# ExtensionConnector.net
KiCad netlist of a schematic drawn in Altium Designer
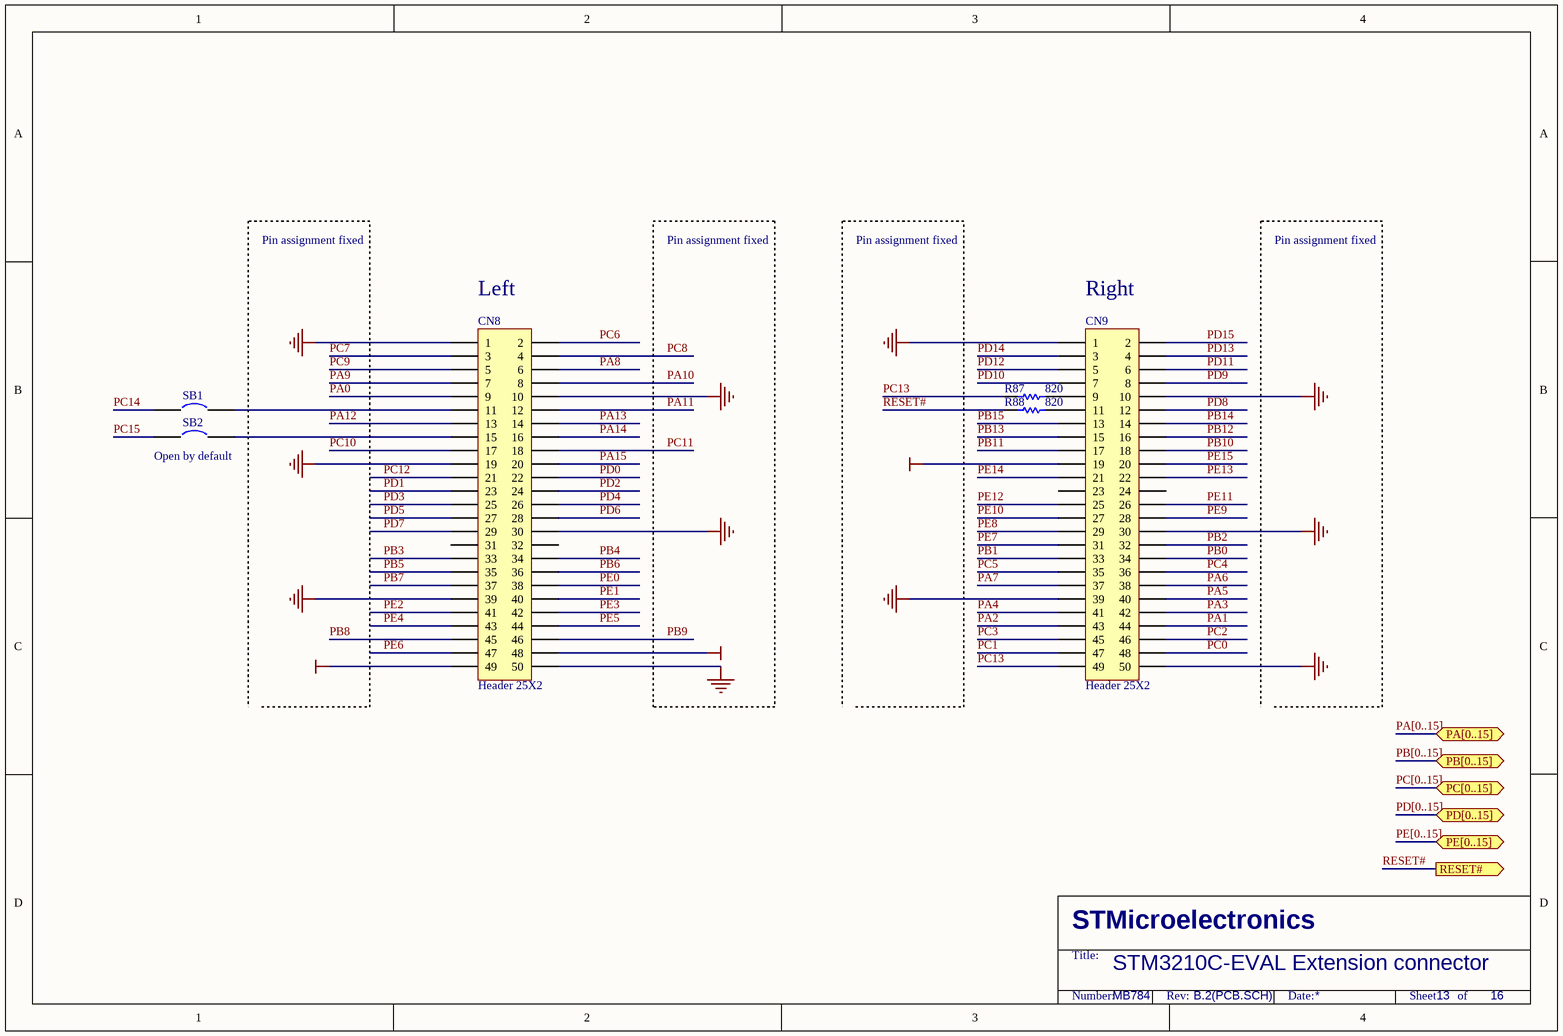
[diagram p0: ExtensionConnector.SchDoc]

(export (version "E")
  (design (tool "Eeschema 10.0.6"))
  (components
    (comp (ref "CN8")
      (value "Header 25X2")
      (footprint "2*25P")
      (description "Header, 25-Pin, Dual row")
      (fields (field (name "PUBLISHER") "Altium Limited"))
      (libsource (lib "Miscellaneous Connectors") (part "Header 25X2"))
    )
    (comp (ref "CN9")
      (value "Header 25X2")
      (footprint "2*25P")
      (description "Header, 25-Pin, Dual row")
      (fields (field (name "PUBLISHER") "Altium Limited"))
      (libsource (lib "Miscellaneous Connectors") (part "Header 25X2"))
    )
    (comp (ref "R87")
      (value "820")
      (footprint "0603R")
      (description "Resistor")
      (fields (field (name "PUBLISHER") "Altium Limited"))
      (libsource (lib "Miscellaneous Devices") (part "Res1"))
    )
    (comp (ref "R88")
      (value "820")
      (footprint "0603R")
      (description "Resistor")
      (fields (field (name "PUBLISHER") "Altium Limited"))
      (libsource (lib "Miscellaneous Devices") (part "Res1"))
    )
    (comp (ref "SB1")
      (value "~")
      (footprint "JP2_SMD")
      (description "Circuit Breaker")
      (fields (field (name "PUBLISHER") "Altium Limited"))
      (libsource (lib "Miscellaneous Devices") (part "Circuit Breaker"))
    )
    (comp (ref "SB2")
      (value "~")
      (footprint "JP2_SMD")
      (description "Circuit Breaker")
      (fields (field (name "PUBLISHER") "Altium Limited"))
      (libsource (lib "Miscellaneous Devices") (part "Circuit Breaker"))
    )
  )
  (nets
    (net (code "1") (name "+3V3") (class "Default")
      (node (ref "CN8") (pin "48") (pinfunction "48_48") (pintype "passive"))
    )
    (net (code "2") (name "/PA0") (class "Default")
      (node (ref "CN8") (pin "9") (pinfunction "9_9") (pintype "passive"))
    )
    (net (code "3") (name "/PA1") (class "Default")
      (node (ref "CN9") (pin "44") (pinfunction "44_44") (pintype "passive"))
    )
    (net (code "4") (name "/PA2") (class "Default")
      (node (ref "CN9") (pin "43") (pinfunction "43_43") (pintype "passive"))
    )
    (net (code "5") (name "/PA3") (class "Default")
      (node (ref "CN9") (pin "42") (pinfunction "42_42") (pintype "passive"))
    )
    (net (code "6") (name "/PA4") (class "Default")
      (node (ref "CN9") (pin "41") (pinfunction "41_41") (pintype "passive"))
    )
    (net (code "7") (name "/PA5") (class "Default")
      (node (ref "CN9") (pin "40") (pinfunction "40_40") (pintype "passive"))
    )
    (net (code "8") (name "/PA6") (class "Default")
      (node (ref "CN9") (pin "38") (pinfunction "38_38") (pintype "passive"))
    )
    (net (code "9") (name "/PA7") (class "Default")
      (node (ref "CN9") (pin "37") (pinfunction "37_37") (pintype "passive"))
    )
    (net (code "10") (name "/PA8") (class "Default")
      (node (ref "CN8") (pin "6") (pinfunction "6_6") (pintype "passive"))
    )
    (net (code "11") (name "/PA9") (class "Default")
      (node (ref "CN8") (pin "7") (pinfunction "7_7") (pintype "passive"))
    )
    (net (code "12") (name "/PA10") (class "Default")
      (node (ref "CN8") (pin "8") (pinfunction "8_8") (pintype "passive"))
    )
    (net (code "13") (name "/PA11") (class "Default")
      (node (ref "CN8") (pin "12") (pinfunction "12_12") (pintype "passive"))
    )
    (net (code "14") (name "/PA12") (class "Default")
      (node (ref "CN8") (pin "13") (pinfunction "13_13") (pintype "passive"))
    )
    (net (code "15") (name "/PA13") (class "Default")
      (node (ref "CN8") (pin "14") (pinfunction "14_14") (pintype "passive"))
    )
    (net (code "16") (name "/PA14") (class "Default")
      (node (ref "CN8") (pin "16") (pinfunction "16_16") (pintype "passive"))
    )
    (net (code "17") (name "/PA15") (class "Default")
      (node (ref "CN8") (pin "20") (pinfunction "20_20") (pintype "passive"))
    )
    (net (code "19") (name "/PB0") (class "Default")
      (node (ref "CN9") (pin "34") (pinfunction "34_34") (pintype "passive"))
    )
    (net (code "20") (name "/PB1") (class "Default")
      (node (ref "CN9") (pin "33") (pinfunction "33_33") (pintype "passive"))
    )
    (net (code "21") (name "/PB2") (class "Default")
      (node (ref "CN9") (pin "32") (pinfunction "32_32") (pintype "passive"))
    )
    (net (code "22") (name "/PB3") (class "Default")
      (node (ref "CN8") (pin "33") (pinfunction "33_33") (pintype "passive"))
    )
    (net (code "23") (name "/PB4") (class "Default")
      (node (ref "CN8") (pin "34") (pinfunction "34_34") (pintype "passive"))
    )
    (net (code "24") (name "/PB5") (class "Default")
      (node (ref "CN8") (pin "35") (pinfunction "35_35") (pintype "passive"))
    )
    (net (code "25") (name "/PB6") (class "Default")
      (node (ref "CN8") (pin "36") (pinfunction "36_36") (pintype "passive"))
    )
    (net (code "26") (name "/PB7") (class "Default")
      (node (ref "CN8") (pin "37") (pinfunction "37_37") (pintype "passive"))
    )
    (net (code "27") (name "/PB8") (class "Default")
      (node (ref "CN8") (pin "45") (pinfunction "45_45") (pintype "passive"))
    )
    (net (code "28") (name "/PB9") (class "Default")
      (node (ref "CN8") (pin "46") (pinfunction "46_46") (pintype "passive"))
    )
    (net (code "29") (name "/PB10") (class "Default")
      (node (ref "CN9") (pin "18") (pinfunction "18_18") (pintype "passive"))
    )
    (net (code "30") (name "/PB11") (class "Default")
      (node (ref "CN9") (pin "17") (pinfunction "17_17") (pintype "passive"))
    )
    (net (code "31") (name "/PB12") (class "Default")
      (node (ref "CN9") (pin "16") (pinfunction "16_16") (pintype "passive"))
    )
    (net (code "32") (name "/PB13") (class "Default")
      (node (ref "CN9") (pin "15") (pinfunction "15_15") (pintype "passive"))
    )
    (net (code "33") (name "/PB14") (class "Default")
      (node (ref "CN9") (pin "14") (pinfunction "14_14") (pintype "passive"))
    )
    (net (code "34") (name "/PB15") (class "Default")
      (node (ref "CN9") (pin "13") (pinfunction "13_13") (pintype "passive"))
    )
    (net (code "36") (name "/PC0") (class "Default")
      (node (ref "CN9") (pin "48") (pinfunction "48_48") (pintype "passive"))
    )
    (net (code "37") (name "/PC1") (class "Default")
      (node (ref "CN9") (pin "47") (pinfunction "47_47") (pintype "passive"))
    )
    (net (code "38") (name "/PC2") (class "Default")
      (node (ref "CN9") (pin "46") (pinfunction "46_46") (pintype "passive"))
    )
    (net (code "39") (name "/PC3") (class "Default")
      (node (ref "CN9") (pin "45") (pinfunction "45_45") (pintype "passive"))
    )
    (net (code "40") (name "/PC4") (class "Default")
      (node (ref "CN9") (pin "36") (pinfunction "36_36") (pintype "passive"))
    )
    (net (code "41") (name "/PC5") (class "Default")
      (node (ref "CN9") (pin "35") (pinfunction "35_35") (pintype "passive"))
    )
    (net (code "42") (name "/PC6") (class "Default")
      (node (ref "CN8") (pin "2") (pinfunction "2_2") (pintype "passive"))
    )
    (net (code "43") (name "/PC7") (class "Default")
      (node (ref "CN8") (pin "3") (pinfunction "3_3") (pintype "passive"))
    )
    (net (code "44") (name "/PC8") (class "Default")
      (node (ref "CN8") (pin "4") (pinfunction "4_4") (pintype "passive"))
    )
    (net (code "45") (name "/PC9") (class "Default")
      (node (ref "CN8") (pin "5") (pinfunction "5_5") (pintype "passive"))
    )
    (net (code "46") (name "/PC10") (class "Default")
      (node (ref "CN8") (pin "17") (pinfunction "17_17") (pintype "passive"))
    )
    (net (code "47") (name "/PC11") (class "Default")
      (node (ref "CN8") (pin "18") (pinfunction "18_18") (pintype "passive"))
    )
    (net (code "48") (name "/PC12") (class "Default")
      (node (ref "CN8") (pin "21") (pinfunction "21_21") (pintype "passive"))
    )
    (net (code "49") (name "/PC13") (class "Default")
      (node (ref "CN9") (pin "49") (pinfunction "49_49") (pintype "passive"))
      (node (ref "R87") (pin "1") (pinfunction "1_1") (pintype "passive"))
    )
    (net (code "50") (name "/PC14") (class "Default")
      (node (ref "SB1") (pin "1") (pinfunction "1_1") (pintype "passive"))
    )
    (net (code "51") (name "/PC15") (class "Default")
      (node (ref "SB2") (pin "1") (pinfunction "1_1") (pintype "passive"))
    )
    (net (code "53") (name "/PD0") (class "Default")
      (node (ref "CN8") (pin "22") (pinfunction "22_22") (pintype "passive"))
    )
    (net (code "54") (name "/PD1") (class "Default")
      (node (ref "CN8") (pin "23") (pinfunction "23_23") (pintype "passive"))
    )
    (net (code "55") (name "/PD2") (class "Default")
      (node (ref "CN8") (pin "24") (pinfunction "24_24") (pintype "passive"))
    )
    (net (code "56") (name "/PD3") (class "Default")
      (node (ref "CN8") (pin "25") (pinfunction "25_25") (pintype "passive"))
    )
    (net (code "57") (name "/PD4") (class "Default")
      (node (ref "CN8") (pin "26") (pinfunction "26_26") (pintype "passive"))
    )
    (net (code "58") (name "/PD5") (class "Default")
      (node (ref "CN8") (pin "27") (pinfunction "27_27") (pintype "passive"))
    )
    (net (code "59") (name "/PD6") (class "Default")
      (node (ref "CN8") (pin "28") (pinfunction "28_28") (pintype "passive"))
    )
    (net (code "60") (name "/PD7") (class "Default")
      (node (ref "CN8") (pin "29") (pinfunction "29_29") (pintype "passive"))
    )
    (net (code "61") (name "/PD8") (class "Default")
      (node (ref "CN9") (pin "12") (pinfunction "12_12") (pintype "passive"))
    )
    (net (code "62") (name "/PD9") (class "Default")
      (node (ref "CN9") (pin "8") (pinfunction "8_8") (pintype "passive"))
    )
    (net (code "63") (name "/PD10") (class "Default")
      (node (ref "CN9") (pin "7") (pinfunction "7_7") (pintype "passive"))
    )
    (net (code "64") (name "/PD11") (class "Default")
      (node (ref "CN9") (pin "6") (pinfunction "6_6") (pintype "passive"))
    )
    (net (code "65") (name "/PD12") (class "Default")
      (node (ref "CN9") (pin "5") (pinfunction "5_5") (pintype "passive"))
    )
    (net (code "66") (name "/PD13") (class "Default")
      (node (ref "CN9") (pin "4") (pinfunction "4_4") (pintype "passive"))
    )
    (net (code "67") (name "/PD14") (class "Default")
      (node (ref "CN9") (pin "3") (pinfunction "3_3") (pintype "passive"))
    )
    (net (code "68") (name "/PD15") (class "Default")
      (node (ref "CN9") (pin "2") (pinfunction "2_2") (pintype "passive"))
    )
    (net (code "70") (name "/PE0") (class "Default")
      (node (ref "CN8") (pin "38") (pinfunction "38_38") (pintype "passive"))
    )
    (net (code "71") (name "/PE1") (class "Default")
      (node (ref "CN8") (pin "40") (pinfunction "40_40") (pintype "passive"))
    )
    (net (code "72") (name "/PE2") (class "Default")
      (node (ref "CN8") (pin "41") (pinfunction "41_41") (pintype "passive"))
    )
    (net (code "73") (name "/PE3") (class "Default")
      (node (ref "CN8") (pin "42") (pinfunction "42_42") (pintype "passive"))
    )
    (net (code "74") (name "/PE4") (class "Default")
      (node (ref "CN8") (pin "43") (pinfunction "43_43") (pintype "passive"))
    )
    (net (code "75") (name "/PE5") (class "Default")
      (node (ref "CN8") (pin "44") (pinfunction "44_44") (pintype "passive"))
    )
    (net (code "76") (name "/PE6") (class "Default")
      (node (ref "CN8") (pin "47") (pinfunction "47_47") (pintype "passive"))
    )
    (net (code "77") (name "/PE7") (class "Default")
      (node (ref "CN9") (pin "31") (pinfunction "31_31") (pintype "passive"))
    )
    (net (code "78") (name "/PE8") (class "Default")
      (node (ref "CN9") (pin "29") (pinfunction "29_29") (pintype "passive"))
    )
    (net (code "79") (name "/PE9") (class "Default")
      (node (ref "CN9") (pin "28") (pinfunction "28_28") (pintype "passive"))
    )
    (net (code "80") (name "/PE10") (class "Default")
      (node (ref "CN9") (pin "27") (pinfunction "27_27") (pintype "passive"))
    )
    (net (code "81") (name "/PE11") (class "Default")
      (node (ref "CN9") (pin "26") (pinfunction "26_26") (pintype "passive"))
    )
    (net (code "82") (name "/PE12") (class "Default")
      (node (ref "CN9") (pin "25") (pinfunction "25_25") (pintype "passive"))
    )
    (net (code "83") (name "/PE13") (class "Default")
      (node (ref "CN9") (pin "22") (pinfunction "22_22") (pintype "passive"))
    )
    (net (code "84") (name "/PE14") (class "Default")
      (node (ref "CN9") (pin "21") (pinfunction "21_21") (pintype "passive"))
    )
    (net (code "85") (name "/PE15") (class "Default")
      (node (ref "CN9") (pin "20") (pinfunction "20_20") (pintype "passive"))
    )
    (net (code "87") (name "/RESET#") (class "Default")
      (node (ref "R88") (pin "2") (pinfunction "2_2") (pintype "passive"))
    )
    (net (code "88") (name "D5V") (class "Default")
      (node (ref "CN8") (pin "49") (pinfunction "49_49") (pintype "passive"))
      (node (ref "CN9") (pin "19") (pinfunction "19_19") (pintype "passive"))
    )
    (net (code "89") (name "GND") (class "Default")
      (node (ref "CN8") (pin "1") (pinfunction "1_1") (pintype "passive"))
      (node (ref "CN8") (pin "10") (pinfunction "10_10") (pintype "passive"))
      (node (ref "CN8") (pin "19") (pinfunction "19_19") (pintype "passive"))
      (node (ref "CN8") (pin "30") (pinfunction "30_30") (pintype "passive"))
      (node (ref "CN8") (pin "39") (pinfunction "39_39") (pintype "passive"))
      (node (ref "CN8") (pin "50") (pinfunction "50_50") (pintype "passive"))
      (node (ref "CN9") (pin "1") (pinfunction "1_1") (pintype "passive"))
      (node (ref "CN9") (pin "10") (pinfunction "10_10") (pintype "passive"))
      (node (ref "CN9") (pin "30") (pinfunction "30_30") (pintype "passive"))
      (node (ref "CN9") (pin "39") (pinfunction "39_39") (pintype "passive"))
      (node (ref "CN9") (pin "50") (pinfunction "50_50") (pintype "passive"))
    )
    (net (code "90") (name "Net-(CN8-Pad11)") (class "Default")
      (node (ref "CN8") (pin "11") (pinfunction "11_11") (pintype "passive"))
      (node (ref "SB1") (pin "2") (pinfunction "2_2") (pintype "passive"))
    )
    (net (code "91") (name "Net-(CN8-Pad15)") (class "Default")
      (node (ref "CN8") (pin "15") (pinfunction "15_15") (pintype "passive"))
      (node (ref "SB2") (pin "2") (pinfunction "2_2") (pintype "passive"))
    )
    (net (code "92") (name "Net-(CN9-Pad9)") (class "Default")
      (node (ref "CN9") (pin "9") (pinfunction "9_9") (pintype "passive"))
      (node (ref "R87") (pin "2") (pinfunction "2_2") (pintype "passive"))
    )
    (net (code "93") (name "Net-(CN9-Pad11)") (class "Default")
      (node (ref "CN9") (pin "11") (pinfunction "11_11") (pintype "passive"))
      (node (ref "R88") (pin "1") (pinfunction "1_1") (pintype "passive"))
    )
    (net (code "94") (name "unconnected-(CN8-Pad31)") (class "Default")
      (node (ref "CN8") (pin "31") (pinfunction "31_31") (pintype "passive"))
    )
    (net (code "95") (name "unconnected-(CN8-Pad32)") (class "Default")
      (node (ref "CN8") (pin "32") (pinfunction "32_32") (pintype "passive"))
    )
    (net (code "96") (name "unconnected-(CN9-Pad23)") (class "Default")
      (node (ref "CN9") (pin "23") (pinfunction "23_23") (pintype "passive"))
    )
    (net (code "97") (name "unconnected-(CN9-Pad24)") (class "Default")
      (node (ref "CN9") (pin "24") (pinfunction "24_24") (pintype "passive"))
    )
  )
)
